# range_anchor.net
KiCad netlist of a schematic drawn in EAGLE
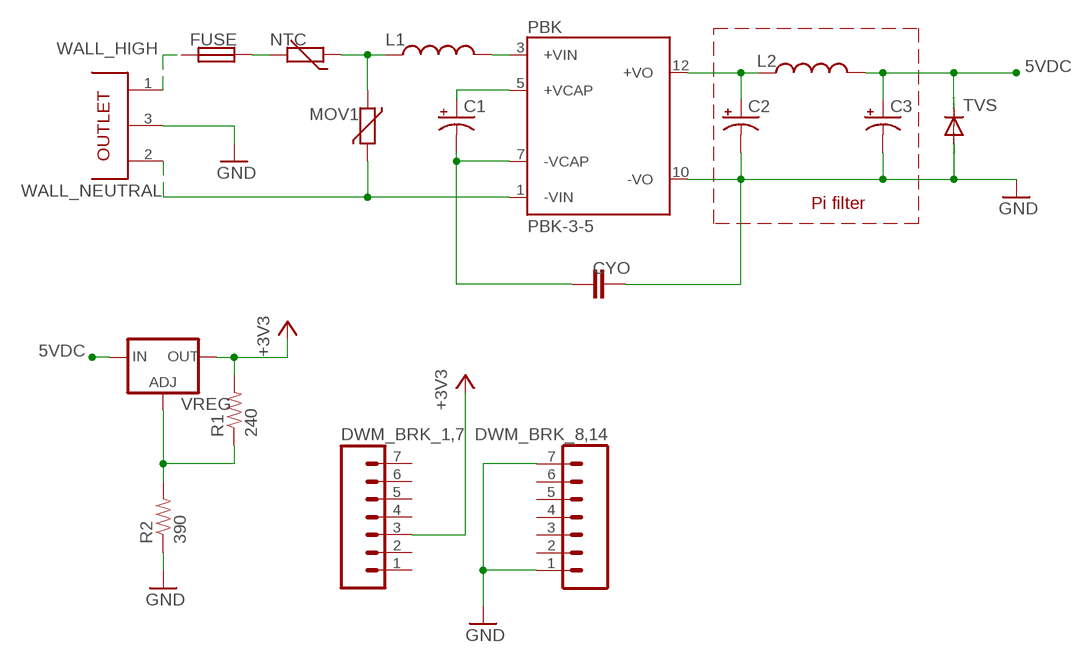
[diagram p0: schematic, sheet 1]

(export (version "E")
  (design (tool "Eeschema 10.0.6"))
  (components
    (comp (ref "C1")
      (value "CAP_POLPTH2")
      (footprint "eagle-import:CPOL-RADIAL-10UF-25V")
      (libsource (lib "eagle-import") (part "CAP_POLPTH2"))
    )
    (comp (ref "C2")
      (value "CAP_POLPTH2")
      (footprint "eagle-import:CPOL-RADIAL-10UF-25V")
      (libsource (lib "eagle-import") (part "CAP_POLPTH2"))
    )
    (comp (ref "C3")
      (value "CAP_POLPTH2")
      (footprint "eagle-import:CPOL-RADIAL-10UF-25V")
      (libsource (lib "eagle-import") (part "CAP_POLPTH2"))
    )
    (comp (ref "CYO")
      (value "CAPPTH3")
      (footprint "eagle-import:CAP-PTH-LARGE")
      (libsource (lib "eagle-import") (part "CAPPTH3"))
    )
    (comp (ref "DWM_BRK_1,7")
      (value "M07LOCK")
      (footprint "eagle-import:1X07_LOCK")
      (libsource (lib "eagle-import") (part "M07LOCK"))
    )
    (comp (ref "DWM_BRK_8,14")
      (value "M07LOCK")
      (footprint "eagle-import:1X07_LOCK")
      (libsource (lib "eagle-import") (part "M07LOCK"))
    )
    (comp (ref "FUSE")
      (value "FUSESMD")
      (footprint "eagle-import:2-SMD")
      (libsource (lib "eagle-import") (part "FUSESMD"))
    )
    (comp (ref "L1")
      (value "INDUCTORAXIAL-0.6")
      (footprint "eagle-import:AXIAL-0.6")
      (libsource (lib "eagle-import") (part "INDUCTORAXIAL-0.6"))
    )
    (comp (ref "L2")
      (value "INDUCTORAXIAL-0.6")
      (footprint "eagle-import:AXIAL-0.6")
      (libsource (lib "eagle-import") (part "INDUCTORAXIAL-0.6"))
    )
    (comp (ref "MOV1")
      (value "VARISTOR-2,5")
      (footprint "eagle-import:R-5")
      (libsource (lib "eagle-import") (part "VARISTOR-2,5"))
    )
    (comp (ref "NTC")
      (value "THERMISTOR-7,5")
      (footprint "eagle-import:R-7,5")
      (libsource (lib "eagle-import") (part "THERMISTOR-7,5"))
    )
    (comp (ref "PBK")
      (value "PBK-3-5")
      (footprint "eagle-import:3-5-VERTICAL")
      (libsource (lib "eagle-import") (part "PBK-3-5"))
    )
    (comp (ref "R1")
      (value "240")
      (footprint "eagle-import:1206")
      (libsource (lib "eagle-import") (part "RESISTOR1206"))
    )
    (comp (ref "R2")
      (value "390")
      (footprint "eagle-import:1206")
      (libsource (lib "eagle-import") (part "RESISTOR1206"))
    )
    (comp (ref "TVS")
      (value "DIODE-DO214AA")
      (footprint "eagle-import:DO214AA")
      (libsource (lib "eagle-import") (part "DIODE-DO214AA"))
    )
    (comp (ref "VREG")
      (value "V_REG_317DPACK")
      (footprint "eagle-import:V-REG_DPACK")
      (libsource (lib "eagle-import") (part "V_REG_317DPACK"))
    )
    (comp (ref "WALL")
      (value "OUTLET")
      (footprint "eagle-import:OUTLET")
      (libsource (lib "eagle-import") (part "OUTLET"))
    )
  )
  (nets
    (net (code "1") (name "+3V3") (class "Default")
      (node (ref "DWM_BRK_1,7") (pin "3") (pinfunction "3_3") (pintype "passive"))
      (node (ref "R1") (pin "2") (pinfunction "2_2") (pintype "passive"))
      (node (ref "VREG") (pin "4") (pinfunction "OUT_4") (pintype "output"))
    )
    (net (code "2") (name "/5VDC") (class "Default")
      (node (ref "C3") (pin "1") (pinfunction "+_1") (pintype "passive"))
      (node (ref "L2") (pin "P$2") (pinfunction "2_P$2") (pintype "passive"))
      (node (ref "TVS") (pin "C") (pinfunction "C_C") (pintype "passive"))
      (node (ref "VREG") (pin "3") (pinfunction "IN_3") (pintype "input"))
    )
    (net (code "3") (name "/WALL_HIGH") (class "Default")
      (node (ref "FUSE") (pin "1") (pinfunction "1_1") (pintype "passive"))
      (node (ref "WALL") (pin "1") (pinfunction "HIGH_1") (pintype "power_in"))
    )
    (net (code "4") (name "/WALL_NEUTRAL") (class "Default")
      (node (ref "MOV1") (pin "2") (pinfunction "2_2") (pintype "passive"))
      (node (ref "PBK") (pin "1") (pinfunction "-VIN_1") (pintype "power_in"))
      (node (ref "WALL") (pin "2") (pinfunction "NEUTRAL_2") (pintype "power_in"))
    )
    (net (code "5") (name "GND") (class "Default")
      (node (ref "C2") (pin "2") (pinfunction "-_2") (pintype "passive"))
      (node (ref "C3") (pin "2") (pinfunction "-_2") (pintype "passive"))
      (node (ref "CYO") (pin "2") (pinfunction "2_2") (pintype "passive"))
      (node (ref "DWM_BRK_8,14") (pin "1") (pinfunction "1_1") (pintype "passive"))
      (node (ref "DWM_BRK_8,14") (pin "7") (pinfunction "7_7") (pintype "passive"))
      (node (ref "PBK") (pin "10") (pinfunction "-VO_10") (pintype "output"))
      (node (ref "R2") (pin "1") (pinfunction "1_1") (pintype "passive"))
      (node (ref "TVS") (pin "A") (pinfunction "A_A") (pintype "passive"))
      (node (ref "WALL") (pin "3") (pinfunction "GND_3") (pintype "power_in"))
    )
    (net (code "6") (name "Net-(C1-+)") (class "Default")
      (node (ref "C1") (pin "1") (pinfunction "+_1") (pintype "passive"))
      (node (ref "PBK") (pin "5") (pinfunction "+VCAP_5") (pintype "power_in"))
    )
    (net (code "7") (name "Net-(C1--)") (class "Default")
      (node (ref "C1") (pin "2") (pinfunction "-_2") (pintype "passive"))
      (node (ref "CYO") (pin "1") (pinfunction "1_1") (pintype "passive"))
      (node (ref "PBK") (pin "7") (pinfunction "-VCAP_7") (pintype "power_in"))
    )
    (net (code "8") (name "Net-(C2-+)") (class "Default")
      (node (ref "C2") (pin "1") (pinfunction "+_1") (pintype "passive"))
      (node (ref "L2") (pin "P$1") (pinfunction "1_P$1") (pintype "passive"))
      (node (ref "PBK") (pin "12") (pinfunction "+VO_12") (pintype "output"))
    )
    (net (code "9") (name "Net-(FUSE-Pad2)") (class "Default")
      (node (ref "FUSE") (pin "2") (pinfunction "2_2") (pintype "passive"))
      (node (ref "NTC") (pin "2") (pinfunction "2_2") (pintype "passive"))
    )
    (net (code "10") (name "Net-(L1-1)") (class "Default")
      (node (ref "L1") (pin "P$1") (pinfunction "1_P$1") (pintype "passive"))
      (node (ref "MOV1") (pin "1") (pinfunction "1_1") (pintype "passive"))
      (node (ref "NTC") (pin "1") (pinfunction "1_1") (pintype "passive"))
    )
    (net (code "11") (name "Net-(L1-2)") (class "Default")
      (node (ref "L1") (pin "P$2") (pinfunction "2_P$2") (pintype "passive"))
      (node (ref "PBK") (pin "3") (pinfunction "+VIN_3") (pintype "power_in"))
    )
    (net (code "12") (name "Net-(VREG-ADJ)") (class "Default")
      (node (ref "R1") (pin "1") (pinfunction "1_1") (pintype "passive"))
      (node (ref "R2") (pin "2") (pinfunction "2_2") (pintype "passive"))
      (node (ref "VREG") (pin "1") (pinfunction "ADJ_1") (pintype "input"))
    )
    (net (code "13") (name "unconnected-(DWM_BRK_1,7-Pad1)") (class "Default")
      (node (ref "DWM_BRK_1,7") (pin "1") (pinfunction "1_1") (pintype "passive"))
    )
    (net (code "14") (name "unconnected-(DWM_BRK_1,7-Pad2)") (class "Default")
      (node (ref "DWM_BRK_1,7") (pin "2") (pinfunction "2_2") (pintype "passive"))
    )
    (net (code "15") (name "unconnected-(DWM_BRK_1,7-Pad4)") (class "Default")
      (node (ref "DWM_BRK_1,7") (pin "4") (pinfunction "4_4") (pintype "passive"))
    )
    (net (code "16") (name "unconnected-(DWM_BRK_1,7-Pad5)") (class "Default")
      (node (ref "DWM_BRK_1,7") (pin "5") (pinfunction "5_5") (pintype "passive"))
    )
    (net (code "17") (name "unconnected-(DWM_BRK_1,7-Pad6)") (class "Default")
      (node (ref "DWM_BRK_1,7") (pin "6") (pinfunction "6_6") (pintype "passive"))
    )
    (net (code "18") (name "unconnected-(DWM_BRK_1,7-Pad7)") (class "Default")
      (node (ref "DWM_BRK_1,7") (pin "7") (pinfunction "7_7") (pintype "passive"))
    )
    (net (code "19") (name "unconnected-(DWM_BRK_8,14-Pad2)") (class "Default")
      (node (ref "DWM_BRK_8,14") (pin "2") (pinfunction "2_2") (pintype "passive"))
    )
    (net (code "20") (name "unconnected-(DWM_BRK_8,14-Pad3)") (class "Default")
      (node (ref "DWM_BRK_8,14") (pin "3") (pinfunction "3_3") (pintype "passive"))
    )
    (net (code "21") (name "unconnected-(DWM_BRK_8,14-Pad4)") (class "Default")
      (node (ref "DWM_BRK_8,14") (pin "4") (pinfunction "4_4") (pintype "passive"))
    )
    (net (code "22") (name "unconnected-(DWM_BRK_8,14-Pad5)") (class "Default")
      (node (ref "DWM_BRK_8,14") (pin "5") (pinfunction "5_5") (pintype "passive"))
    )
    (net (code "23") (name "unconnected-(DWM_BRK_8,14-Pad6)") (class "Default")
      (node (ref "DWM_BRK_8,14") (pin "6") (pinfunction "6_6") (pintype "passive"))
    )
  )
)
